# interface.net
KiCad netlist of a schematic drawn in Altium Designer
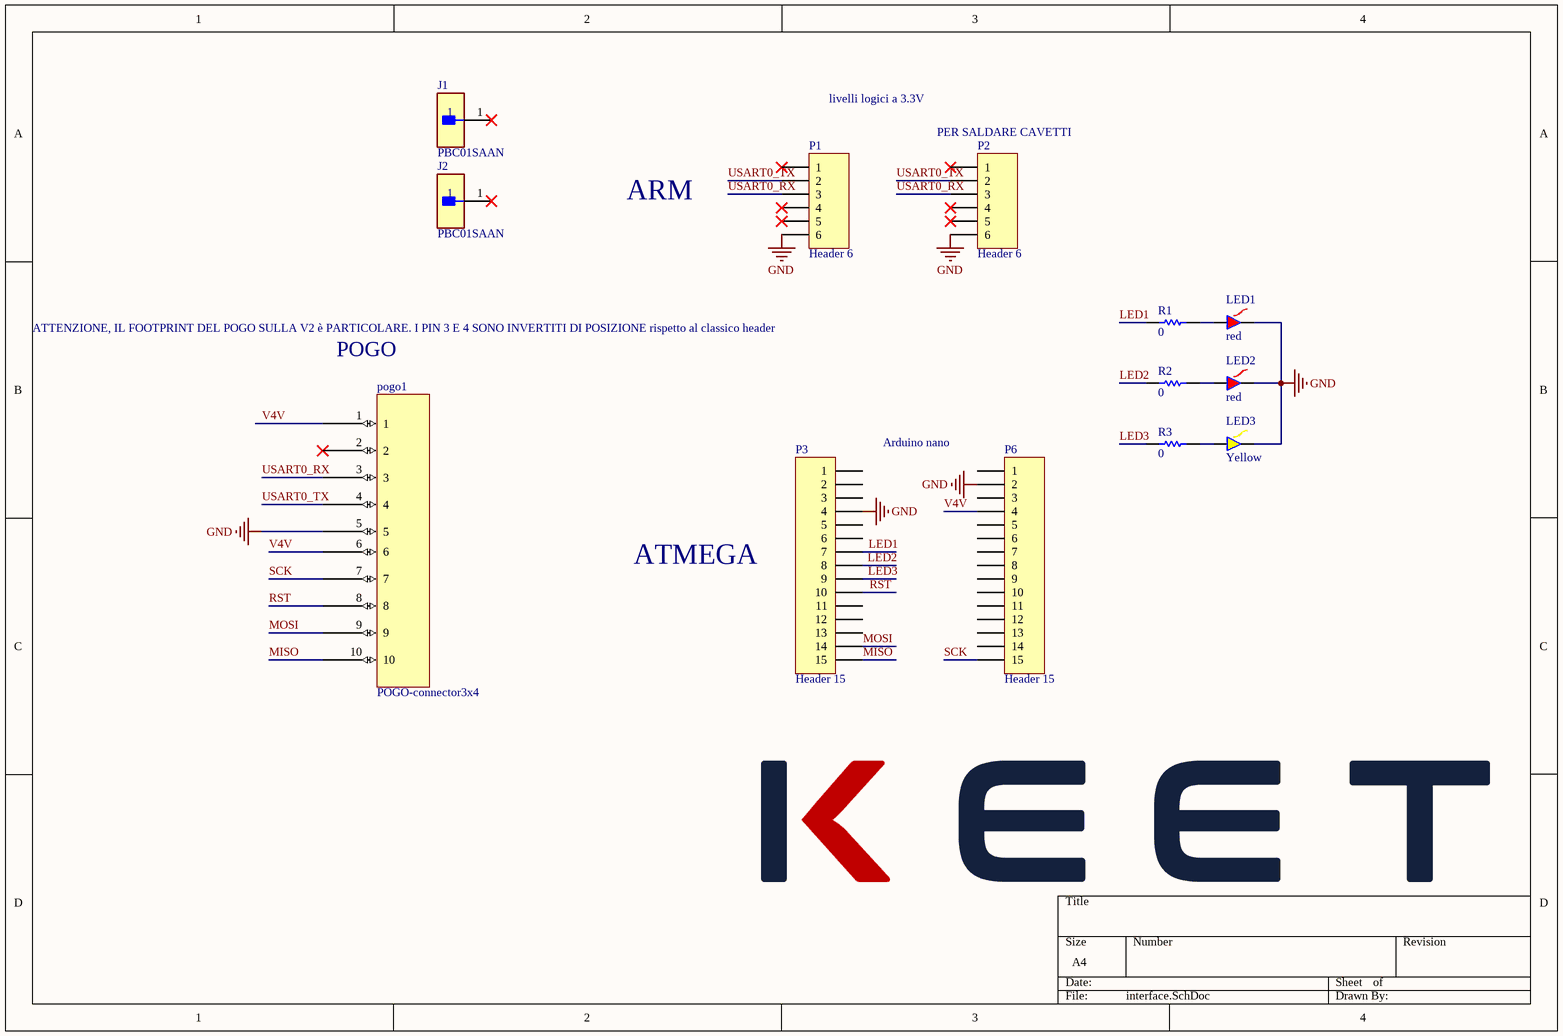
[diagram p0: interface.SchDoc]

(export (version "E")
  (design (tool "Eeschema 10.0.6"))
  (components
    (comp (ref "J1")
      (value "PBC01SAAN")
      (footprint "FP-PBC01SAAN-MFG")
      (description "CONN HEADER VERT 1POS")
      (libsource (lib "Altium Content Vault") (part "dd45045ce8184df9e99e12baf3f412c"))
    )
    (comp (ref "J2")
      (value "PBC01SAAN")
      (footprint "FP-PBC01SAAN-MFG")
      (description "CONN HEADER VERT 1POS")
      (libsource (lib "Altium Content Vault") (part "dd45045ce8184df9e99e12baf3f412c"))
    )
    (comp (ref "LED1")
      (value "red")
      (footprint "CAC-0P80X160-2N_ver2")
      (description "AVAGO TECHNOLOGIES - HSMS-C190 - LED, RED, 10MCD, 626NM")
      (fields
        (field (name "MANUFACTURER") "Broadcom Avago")
        (field (name "MANUFACTURER PART NUMBER") "HSMS-C190")
      )
      (libsource (lib "Integrated_Library1") (part "HSMS-C190"))
    )
    (comp (ref "LED2")
      (value "red")
      (footprint "CAC-0P80X160-2N_ver2")
      (description "AVAGO TECHNOLOGIES - HSMS-C190 - LED, RED, 10MCD, 626NM")
      (fields
        (field (name "MANUFACTURER") "Broadcom Avago")
        (field (name "MANUFACTURER PART NUMBER") "HSMS-C190")
      )
      (libsource (lib "Integrated_Library1") (part "HSMS-C190"))
    )
    (comp (ref "LED3")
      (value "Yellow")
      (footprint "CAC-0P80X160-2N_ver2")
      (fields
        (field (name "MANUFACTURER") "Broadcom Avago")
        (field (name "MANUFACTURER PART NUMBER") "HSMY-C190")
      )
      (libsource (lib "Integrated_Library1") (part "HSMY-C190"))
    )
    (comp (ref "P1")
      (value "Header 6")
      (footprint "HDR1X6")
      (description "Header, 6-Pin")
      (fields (field (name "PUBLISHER") "Altium Limited"))
      (libsource (lib "Miscellaneous Connectors") (part "Header 6"))
    )
    (comp (ref "P2")
      (value "Header 6")
      (footprint "HDR1X6")
      (description "Header, 6-Pin")
      (fields (field (name "PUBLISHER") "Altium Limited"))
      (libsource (lib "Miscellaneous Connectors") (part "Header 6"))
    )
    (comp (ref "P3")
      (value "Header 15")
      (footprint "HDR1X15")
      (description "Header, 15-Pin")
      (fields (field (name "PUBLISHER") "Altium Limited"))
      (libsource (lib "Miscellaneous Connectors") (part "Header 15"))
    )
    (comp (ref "P6")
      (value "Header 15")
      (footprint "HDR1X15")
      (description "Header, 15-Pin")
      (fields (field (name "PUBLISHER") "Altium Limited"))
      (libsource (lib "") (part "Header 15_1"))
    )
    (comp (ref "pogo1")
      (value "POGO-connector3x4")
      (footprint "POGO_fisico")
      (description "pad layout for external pogo connector")
      (libsource (lib "Integrated_Library1") (part "POGO-connector3x4"))
    )
    (comp (ref "R1")
      (value "0")
      (footprint "RESC1608X04N")
      (description "YAGEO - RC0603JR-130RL - RES, THICK FILM, 0R, 0.1W, 0603")
      (fields
        (field (name "MANUFACTURER") "Yageo")
        (field (name "MANUFACTURER PART NUMBER") "RC0603JR-130RL")
      )
      (libsource (lib "Integrated_Library1") (part "RC0603JR-130RL"))
    )
    (comp (ref "R2")
      (value "0")
      (footprint "RESC1608X04N")
      (description "YAGEO - RC0603JR-130RL - RES, THICK FILM, 0R, 0.1W, 0603")
      (fields
        (field (name "MANUFACTURER") "Yageo")
        (field (name "MANUFACTURER PART NUMBER") "RC0603JR-130RL")
      )
      (libsource (lib "Integrated_Library1") (part "RC0603JR-130RL"))
    )
    (comp (ref "R3")
      (value "0")
      (footprint "RESC1608X04N")
      (description "YAGEO - RC0603JR-130RL - RES, THICK FILM, 0R, 0.1W, 0603")
      (fields
        (field (name "MANUFACTURER") "Yageo")
        (field (name "MANUFACTURER PART NUMBER") "RC0603JR-130RL")
      )
      (libsource (lib "Integrated_Library1") (part "RC0603JR-130RL"))
    )
  )
  (nets
    (net (code "1") (name "/LED1") (class "Default")
      (node (ref "P3") (pin "7") (pinfunction "7_7") (pintype "passive"))
      (node (ref "R1") (pin "1") (pinfunction "1_1") (pintype "passive"))
    )
    (net (code "2") (name "/LED2") (class "Default")
      (node (ref "P3") (pin "8") (pinfunction "8_8") (pintype "passive"))
      (node (ref "R2") (pin "1") (pinfunction "1_1") (pintype "passive"))
    )
    (net (code "3") (name "/LED3") (class "Default")
      (node (ref "P3") (pin "9") (pinfunction "9_9") (pintype "passive"))
      (node (ref "R3") (pin "1") (pinfunction "1_1") (pintype "passive"))
    )
    (net (code "4") (name "/MISO") (class "Default")
      (node (ref "P3") (pin "15") (pinfunction "15_15") (pintype "passive"))
      (node (ref "pogo1") (pin "10") (pinfunction "10_10") (pintype "bidirectional"))
    )
    (net (code "5") (name "/MOSI") (class "Default")
      (node (ref "P3") (pin "14") (pinfunction "14_14") (pintype "passive"))
      (node (ref "pogo1") (pin "9") (pinfunction "9_9") (pintype "bidirectional"))
    )
    (net (code "6") (name "/RST") (class "Default")
      (node (ref "P3") (pin "10") (pinfunction "10_10") (pintype "passive"))
      (node (ref "pogo1") (pin "8") (pinfunction "8_8") (pintype "bidirectional"))
    )
    (net (code "7") (name "/SCK") (class "Default")
      (node (ref "P6") (pin "15") (pinfunction "15_15") (pintype "passive"))
      (node (ref "pogo1") (pin "7") (pinfunction "7_7") (pintype "bidirectional"))
    )
    (net (code "8") (name "/USART0_RX") (class "Default")
      (node (ref "P1") (pin "3") (pinfunction "3_3") (pintype "passive"))
      (node (ref "P2") (pin "3") (pinfunction "3_3") (pintype "passive"))
      (node (ref "pogo1") (pin "3") (pinfunction "3_3") (pintype "bidirectional"))
    )
    (net (code "9") (name "/USART0_TX") (class "Default")
      (node (ref "P1") (pin "2") (pinfunction "2_2") (pintype "passive"))
      (node (ref "P2") (pin "2") (pinfunction "2_2") (pintype "passive"))
      (node (ref "pogo1") (pin "4") (pinfunction "4_4") (pintype "bidirectional"))
    )
    (net (code "10") (name "/V4V") (class "Default")
      (node (ref "P6") (pin "4") (pinfunction "4_4") (pintype "passive"))
      (node (ref "pogo1") (pin "1") (pinfunction "1_1") (pintype "bidirectional"))
      (node (ref "pogo1") (pin "6") (pinfunction "6_6") (pintype "bidirectional"))
    )
    (net (code "11") (name "GND") (class "Default")
      (node (ref "LED1") (pin "1") (pinfunction "K_1") (pintype "passive"))
      (node (ref "LED2") (pin "1") (pinfunction "K_1") (pintype "passive"))
      (node (ref "LED3") (pin "1") (pinfunction "K_1") (pintype "passive"))
      (node (ref "P1") (pin "6") (pinfunction "6_6") (pintype "passive"))
      (node (ref "P2") (pin "6") (pinfunction "6_6") (pintype "passive"))
      (node (ref "P3") (pin "4") (pinfunction "4_4") (pintype "passive"))
      (node (ref "P6") (pin "2") (pinfunction "2_2") (pintype "passive"))
      (node (ref "pogo1") (pin "5") (pinfunction "5_5") (pintype "bidirectional"))
    )
    (net (code "12") (name "Net-(LED1-A)") (class "Default")
      (node (ref "LED1") (pin "2") (pinfunction "A_2") (pintype "passive"))
      (node (ref "R1") (pin "2") (pinfunction "2_2") (pintype "passive"))
    )
    (net (code "13") (name "Net-(LED2-A)") (class "Default")
      (node (ref "LED2") (pin "2") (pinfunction "A_2") (pintype "passive"))
      (node (ref "R2") (pin "2") (pinfunction "2_2") (pintype "passive"))
    )
    (net (code "14") (name "Net-(LED3-A)") (class "Default")
      (node (ref "LED3") (pin "2") (pinfunction "A_2") (pintype "passive"))
      (node (ref "R3") (pin "2") (pinfunction "2_2") (pintype "passive"))
    )
    (net (code "15") (name "unconnected-(J1-Pad1)") (class "Default")
      (node (ref "J1") (pin "1") (pinfunction "1_1") (pintype "passive+no_connect"))
    )
    (net (code "16") (name "unconnected-(J2-Pad1)") (class "Default")
      (node (ref "J2") (pin "1") (pinfunction "1_1") (pintype "passive+no_connect"))
    )
    (net (code "17") (name "unconnected-(P1-Pad1)") (class "Default")
      (node (ref "P1") (pin "1") (pinfunction "1_1") (pintype "passive+no_connect"))
    )
    (net (code "18") (name "unconnected-(P1-Pad4)") (class "Default")
      (node (ref "P1") (pin "4") (pinfunction "4_4") (pintype "passive+no_connect"))
    )
    (net (code "19") (name "unconnected-(P1-Pad5)") (class "Default")
      (node (ref "P1") (pin "5") (pinfunction "5_5") (pintype "passive+no_connect"))
    )
    (net (code "20") (name "unconnected-(P2-Pad1)") (class "Default")
      (node (ref "P2") (pin "1") (pinfunction "1_1") (pintype "passive+no_connect"))
    )
    (net (code "21") (name "unconnected-(P2-Pad4)") (class "Default")
      (node (ref "P2") (pin "4") (pinfunction "4_4") (pintype "passive+no_connect"))
    )
    (net (code "22") (name "unconnected-(P2-Pad5)") (class "Default")
      (node (ref "P2") (pin "5") (pinfunction "5_5") (pintype "passive+no_connect"))
    )
    (net (code "23") (name "unconnected-(P3-Pad1)") (class "Default")
      (node (ref "P3") (pin "1") (pinfunction "1_1") (pintype "passive"))
    )
    (net (code "24") (name "unconnected-(P3-Pad2)") (class "Default")
      (node (ref "P3") (pin "2") (pinfunction "2_2") (pintype "passive"))
    )
    (net (code "25") (name "unconnected-(P3-Pad3)") (class "Default")
      (node (ref "P3") (pin "3") (pinfunction "3_3") (pintype "passive"))
    )
    (net (code "26") (name "unconnected-(P3-Pad5)") (class "Default")
      (node (ref "P3") (pin "5") (pinfunction "5_5") (pintype "passive"))
    )
    (net (code "27") (name "unconnected-(P3-Pad6)") (class "Default")
      (node (ref "P3") (pin "6") (pinfunction "6_6") (pintype "passive"))
    )
    (net (code "28") (name "unconnected-(P3-Pad11)") (class "Default")
      (node (ref "P3") (pin "11") (pinfunction "11_11") (pintype "passive"))
    )
    (net (code "29") (name "unconnected-(P3-Pad12)") (class "Default")
      (node (ref "P3") (pin "12") (pinfunction "12_12") (pintype "passive"))
    )
    (net (code "30") (name "unconnected-(P3-Pad13)") (class "Default")
      (node (ref "P3") (pin "13") (pinfunction "13_13") (pintype "passive"))
    )
    (net (code "31") (name "unconnected-(P6-Pad1)") (class "Default")
      (node (ref "P6") (pin "1") (pinfunction "1_1") (pintype "passive"))
    )
    (net (code "32") (name "unconnected-(P6-Pad3)") (class "Default")
      (node (ref "P6") (pin "3") (pinfunction "3_3") (pintype "passive"))
    )
    (net (code "33") (name "unconnected-(P6-Pad5)") (class "Default")
      (node (ref "P6") (pin "5") (pinfunction "5_5") (pintype "passive"))
    )
    (net (code "34") (name "unconnected-(P6-Pad6)") (class "Default")
      (node (ref "P6") (pin "6") (pinfunction "6_6") (pintype "passive"))
    )
    (net (code "35") (name "unconnected-(P6-Pad7)") (class "Default")
      (node (ref "P6") (pin "7") (pinfunction "7_7") (pintype "passive"))
    )
    (net (code "36") (name "unconnected-(P6-Pad8)") (class "Default")
      (node (ref "P6") (pin "8") (pinfunction "8_8") (pintype "passive"))
    )
    (net (code "37") (name "unconnected-(P6-Pad9)") (class "Default")
      (node (ref "P6") (pin "9") (pinfunction "9_9") (pintype "passive"))
    )
    (net (code "38") (name "unconnected-(P6-Pad10)") (class "Default")
      (node (ref "P6") (pin "10") (pinfunction "10_10") (pintype "passive"))
    )
    (net (code "39") (name "unconnected-(P6-Pad11)") (class "Default")
      (node (ref "P6") (pin "11") (pinfunction "11_11") (pintype "passive"))
    )
    (net (code "40") (name "unconnected-(P6-Pad12)") (class "Default")
      (node (ref "P6") (pin "12") (pinfunction "12_12") (pintype "passive"))
    )
    (net (code "41") (name "unconnected-(P6-Pad13)") (class "Default")
      (node (ref "P6") (pin "13") (pinfunction "13_13") (pintype "passive"))
    )
    (net (code "42") (name "unconnected-(P6-Pad14)") (class "Default")
      (node (ref "P6") (pin "14") (pinfunction "14_14") (pintype "passive"))
    )
    (net (code "43") (name "unconnected-(pogo1-Pad2)") (class "Default")
      (node (ref "pogo1") (pin "2") (pinfunction "2_2") (pintype "bidirectional+no_connect"))
    )
  )
)
